# Key_RGB_Sensor_Uart.net
KiCad netlist of a schematic drawn in Altium Designer
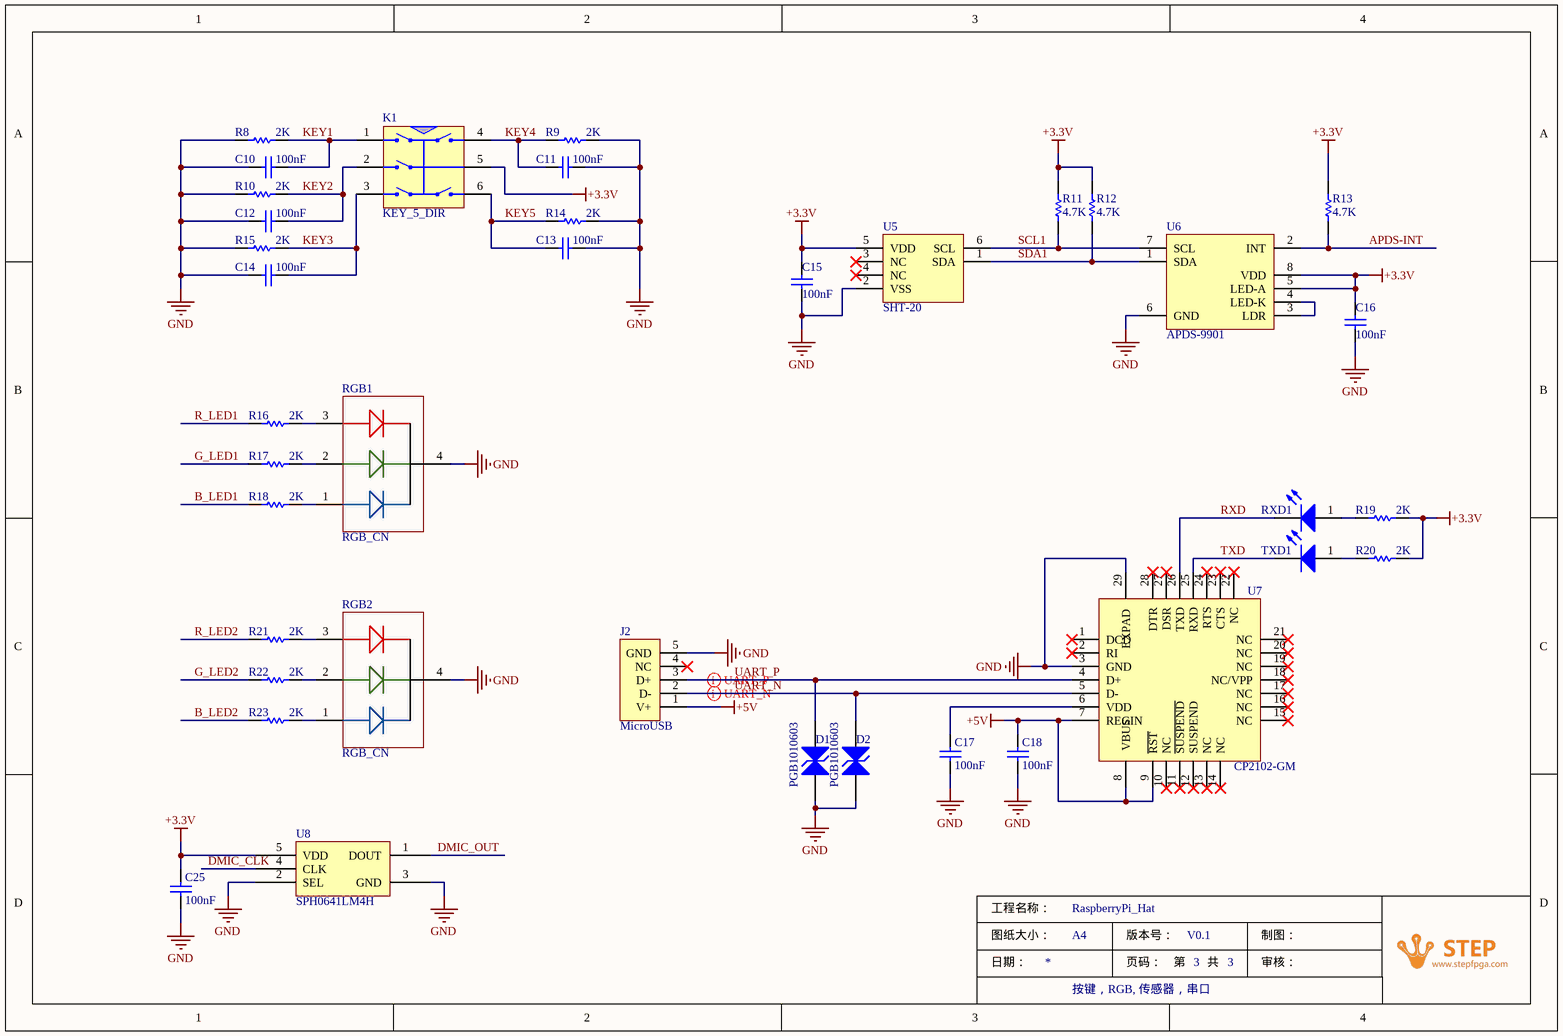
[diagram p0: Key_RGB_Sensor_Uart.SchDoc]

(export (version "E")
  (design (tool "Eeschema 10.0.6"))
  (components
    (comp (ref "C10")
      (value "100nF")
      (footprint "C0603")
      (description "Capacitor (Semiconductor SIM Model)")
      (fields (field (name "PUBLISHER") "Altium Limited"))
      (libsource (lib "Miscellaneous Devices") (part "Cap Semi"))
    )
    (comp (ref "C11")
      (value "100nF")
      (footprint "C0603")
      (description "Capacitor (Semiconductor SIM Model)")
      (fields (field (name "PUBLISHER") "Altium Limited"))
      (libsource (lib "Miscellaneous Devices") (part "Cap Semi"))
    )
    (comp (ref "C12")
      (value "100nF")
      (footprint "C0603")
      (description "Capacitor (Semiconductor SIM Model)")
      (fields (field (name "PUBLISHER") "Altium Limited"))
      (libsource (lib "Miscellaneous Devices") (part "Cap Semi"))
    )
    (comp (ref "C13")
      (value "100nF")
      (footprint "C0603")
      (description "Capacitor (Semiconductor SIM Model)")
      (fields (field (name "PUBLISHER") "Altium Limited"))
      (libsource (lib "Miscellaneous Devices") (part "Cap Semi"))
    )
    (comp (ref "C14")
      (value "100nF")
      (footprint "C0603")
      (description "Capacitor (Semiconductor SIM Model)")
      (fields (field (name "PUBLISHER") "Altium Limited"))
      (libsource (lib "Miscellaneous Devices") (part "Cap Semi"))
    )
    (comp (ref "C15")
      (value "100nF")
      (footprint "C0603")
      (description "Capacitor (Semiconductor SIM Model)")
      (fields (field (name "PUBLISHER") "Altium Limited"))
      (libsource (lib "Miscellaneous Devices") (part "Cap Semi"))
    )
    (comp (ref "C16")
      (value "100nF")
      (footprint "C0603")
      (description "Capacitor (Semiconductor SIM Model)")
      (fields (field (name "PUBLISHER") "Altium Limited"))
      (libsource (lib "Miscellaneous Devices") (part "Cap Semi"))
    )
    (comp (ref "C17")
      (value "100nF")
      (footprint "C0603")
      (description "Capacitor")
      (fields (field (name "PUBLISHER") "Altium Limited"))
      (libsource (lib "Miscellaneous Devices") (part "Cap"))
    )
    (comp (ref "C18")
      (value "100nF")
      (footprint "C0603")
      (description "Capacitor")
      (fields (field (name "PUBLISHER") "Altium Limited"))
      (libsource (lib "Miscellaneous Devices") (part "Cap"))
    )
    (comp (ref "C25")
      (value "100nF")
      (footprint "C0603")
      (description "Capacitor")
      (fields (field (name "PUBLISHER") "Altium Limited"))
      (libsource (lib "Miscellaneous Devices") (part "Cap"))
    )
    (comp (ref "D1")
      (value "PGB1010603")
      (footprint "C0603")
      (description "ESD 抑制器 0603 24VDC .06pF")
      (libsource (lib "FPGA DIP40") (part "PGB1010603"))
    )
    (comp (ref "D2")
      (value "PGB1010603")
      (footprint "C0603")
      (description "ESD 抑制器 0603 24VDC .06pF")
      (libsource (lib "FPGA DIP40") (part "PGB1010603"))
    )
    (comp (ref "J2")
      (value "MicroUSB")
      (footprint "MICRO_USB_4")
      (description "Micro USB Header")
      (libsource (lib "FPGA DIP40") (part "Micro USB Header"))
    )
    (comp (ref "K1")
      (value "KEY_5_DIR")
      (footprint "KEY-CH5")
      (description "五向按键开关，摇杆")
      (libsource (lib "wanganran") (part "KEY_5_DIR"))
    )
    (comp (ref "R8")
      (value "2K")
      (footprint "R0603")
      (description "Resistor")
      (fields (field (name "PUBLISHER") "Altium Limited"))
      (libsource (lib "Miscellaneous Devices") (part "Res1"))
    )
    (comp (ref "R9")
      (value "2K")
      (footprint "R0603")
      (description "Resistor")
      (fields (field (name "PUBLISHER") "Altium Limited"))
      (libsource (lib "Miscellaneous Devices") (part "Res1"))
    )
    (comp (ref "R10")
      (value "2K")
      (footprint "R0603")
      (description "Resistor")
      (fields (field (name "PUBLISHER") "Altium Limited"))
      (libsource (lib "Miscellaneous Devices") (part "Res1"))
    )
    (comp (ref "R11")
      (value "4.7K")
      (footprint "R0603")
      (description "Resistor")
      (fields (field (name "PUBLISHER") "Altium Limited"))
      (libsource (lib "Miscellaneous Devices") (part "Res1"))
    )
    (comp (ref "R12")
      (value "4.7K")
      (footprint "R0603")
      (description "Resistor")
      (fields (field (name "PUBLISHER") "Altium Limited"))
      (libsource (lib "Miscellaneous Devices") (part "Res1"))
    )
    (comp (ref "R13")
      (value "4.7K")
      (footprint "R0603")
      (description "Resistor")
      (fields (field (name "PUBLISHER") "Altium Limited"))
      (libsource (lib "Miscellaneous Devices") (part "Res1"))
    )
    (comp (ref "R14")
      (value "2K")
      (footprint "R0603")
      (description "Resistor")
      (fields (field (name "PUBLISHER") "Altium Limited"))
      (libsource (lib "Miscellaneous Devices") (part "Res1"))
    )
    (comp (ref "R15")
      (value "2K")
      (footprint "R0603")
      (description "Resistor")
      (fields (field (name "PUBLISHER") "Altium Limited"))
      (libsource (lib "Miscellaneous Devices") (part "Res1"))
    )
    (comp (ref "R16")
      (value "2K")
      (footprint "R0603")
      (description "Resistor")
      (fields (field (name "PUBLISHER") "Altium Limited"))
      (libsource (lib "Miscellaneous Devices") (part "Res1"))
    )
    (comp (ref "R17")
      (value "2K")
      (footprint "R0603")
      (description "Resistor")
      (fields (field (name "PUBLISHER") "Altium Limited"))
      (libsource (lib "Miscellaneous Devices") (part "Res1"))
    )
    (comp (ref "R18")
      (value "2K")
      (footprint "R0603")
      (description "Resistor")
      (fields (field (name "PUBLISHER") "Altium Limited"))
      (libsource (lib "Miscellaneous Devices") (part "Res1"))
    )
    (comp (ref "R19")
      (value "2K")
      (footprint "R0603")
      (description "Resistor")
      (fields (field (name "PUBLISHER") "Altium Limited"))
      (libsource (lib "Miscellaneous Devices") (part "Res1"))
    )
    (comp (ref "R20")
      (value "2K")
      (footprint "R0603")
      (description "Resistor")
      (fields (field (name "PUBLISHER") "Altium Limited"))
      (libsource (lib "Miscellaneous Devices") (part "Res1"))
    )
    (comp (ref "R21")
      (value "2K")
      (footprint "R0603")
      (description "Resistor")
      (fields (field (name "PUBLISHER") "Altium Limited"))
      (libsource (lib "Miscellaneous Devices") (part "Res1"))
    )
    (comp (ref "R22")
      (value "2K")
      (footprint "R0603")
      (description "Resistor")
      (fields (field (name "PUBLISHER") "Altium Limited"))
      (libsource (lib "Miscellaneous Devices") (part "Res1"))
    )
    (comp (ref "R23")
      (value "2K")
      (footprint "R0603")
      (description "Resistor")
      (fields (field (name "PUBLISHER") "Altium Limited"))
      (libsource (lib "Miscellaneous Devices") (part "Res1"))
    )
    (comp (ref "RGB1")
      (value "RGB_CN")
      (footprint "RGB_LEDCN")
      (libsource (lib "RaspberryPi_Hat_schlib") (part "RGB_CN"))
    )
    (comp (ref "RGB2")
      (value "RGB_CN")
      (footprint "RGB_LEDCN")
      (libsource (lib "RaspberryPi_Hat_schlib") (part "RGB_CN"))
    )
    (comp (ref "RXD1")
      (value "LED")
      (footprint "LED0603")
      (description "Typical INFRARED GaAs LED,1.8V,10mA,Red")
      (libsource (lib "fpga_board") (part "LED"))
    )
    (comp (ref "TXD1")
      (value "LED")
      (footprint "LED0603")
      (description "Typical INFRARED GaAs LED,1.8V,10mA,Red")
      (libsource (lib "fpga_board") (part "LED"))
    )
    (comp (ref "U5")
      (value "SHT-20")
      (footprint "SHT20")
      (description "温湿度传感器")
      (libsource (lib "step") (part "SHT-20"))
    )
    (comp (ref "U6")
      (value "APDS-9901")
      (footprint "APDS9901")
      (description "接近式传感器")
      (libsource (lib "step") (part "APDS-9901"))
    )
    (comp (ref "U7")
      (value "CP2102-GM")
      (footprint "QFN5*5_28")
      (description "CP2102，USB转串口UART驱动芯片")
      (libsource (lib "wanganran") (part "CP2102"))
    )
    (comp (ref "U8")
      (value "SPH0641LM4H")
      (footprint "SPH(3.5*2.65)")
      (description "数字麦克风")
      (libsource (lib "RaspberryPi_Hat_schlib") (part "SPH0641LM4H"))
    )
  )
  (nets
    (net (code "1") (name "+3.3V") (class "Default")
      (node (ref "C15") (pin "2") (pinfunction "2_2") (pintype "passive"))
      (node (ref "C16") (pin "2") (pinfunction "2_2") (pintype "passive"))
      (node (ref "C25") (pin "2") (pinfunction "2_2") (pintype "passive"))
      (node (ref "K1") (pin "5") (pinfunction "COM_5") (pintype "passive"))
      (node (ref "R11") (pin "2") (pinfunction "2_2") (pintype "passive"))
      (node (ref "R12") (pin "2") (pinfunction "2_2") (pintype "passive"))
      (node (ref "R13") (pin "2") (pinfunction "2_2") (pintype "passive"))
      (node (ref "R19") (pin "1") (pinfunction "1_1") (pintype "passive"))
      (node (ref "R20") (pin "1") (pinfunction "1_1") (pintype "passive"))
      (node (ref "U5") (pin "5") (pinfunction "VDD_5") (pintype "passive"))
      (node (ref "U6") (pin "5") (pinfunction "LED-A_5") (pintype "passive"))
      (node (ref "U6") (pin "8") (pinfunction "VDD_8") (pintype "passive"))
      (node (ref "U8") (pin "5") (pinfunction "VDD_5") (pintype "passive"))
    )
    (net (code "2") (name "+5V") (class "Default")
      (node (ref "C18") (pin "2") (pinfunction "2_2") (pintype "passive"))
      (node (ref "J2") (pin "1") (pinfunction "V+_1") (pintype "passive"))
      (node (ref "U7") (pin "7") (pinfunction "REGIN_7") (pintype "passive"))
      (node (ref "U7") (pin "8") (pinfunction "VBUS_8") (pintype "passive"))
      (node (ref "U7") (pin "9") (pinfunction "~{RST}_9") (pintype "passive"))
    )
    (net (code "3") (name "/APDS-INT") (class "Default")
      (node (ref "R13") (pin "1") (pinfunction "1_1") (pintype "passive"))
      (node (ref "U6") (pin "2") (pinfunction "INT_2") (pintype "passive"))
    )
    (net (code "4") (name "/B_LED1") (class "Default")
      (node (ref "R18") (pin "2") (pinfunction "2_2") (pintype "passive"))
    )
    (net (code "5") (name "/B_LED2") (class "Default")
      (node (ref "R23") (pin "2") (pinfunction "2_2") (pintype "passive"))
    )
    (net (code "6") (name "/DMIC_CLK") (class "Default")
      (node (ref "U8") (pin "4") (pinfunction "CLK_4") (pintype "passive"))
    )
    (net (code "7") (name "/DMIC_OUT") (class "Default")
      (node (ref "U8") (pin "1") (pinfunction "DOUT_1") (pintype "passive"))
    )
    (net (code "8") (name "/G_LED1") (class "Default")
      (node (ref "R17") (pin "2") (pinfunction "2_2") (pintype "passive"))
    )
    (net (code "9") (name "/G_LED2") (class "Default")
      (node (ref "R22") (pin "2") (pinfunction "2_2") (pintype "passive"))
    )
    (net (code "10") (name "/KEY1") (class "Default")
      (node (ref "C10") (pin "1") (pinfunction "1_1") (pintype "passive"))
      (node (ref "K1") (pin "1") (pinfunction "COM_1") (pintype "passive"))
      (node (ref "R8") (pin "1") (pinfunction "1_1") (pintype "passive"))
    )
    (net (code "11") (name "/KEY2") (class "Default")
      (node (ref "C12") (pin "1") (pinfunction "1_1") (pintype "passive"))
      (node (ref "K1") (pin "2") (pinfunction "COM_2") (pintype "passive"))
      (node (ref "R10") (pin "1") (pinfunction "1_1") (pintype "passive"))
    )
    (net (code "12") (name "/KEY3") (class "Default")
      (node (ref "C14") (pin "1") (pinfunction "1_1") (pintype "passive"))
      (node (ref "K1") (pin "3") (pinfunction "COM_3") (pintype "passive"))
      (node (ref "R15") (pin "1") (pinfunction "1_1") (pintype "passive"))
    )
    (net (code "13") (name "/KEY4") (class "Default")
      (node (ref "C11") (pin "2") (pinfunction "2_2") (pintype "passive"))
      (node (ref "K1") (pin "4") (pinfunction "COM_4") (pintype "passive"))
      (node (ref "R9") (pin "2") (pinfunction "2_2") (pintype "passive"))
    )
    (net (code "14") (name "/KEY5") (class "Default")
      (node (ref "C13") (pin "2") (pinfunction "2_2") (pintype "passive"))
      (node (ref "K1") (pin "6") (pinfunction "COM_6") (pintype "passive"))
      (node (ref "R14") (pin "2") (pinfunction "2_2") (pintype "passive"))
    )
    (net (code "15") (name "/RXD") (class "Default")
      (node (ref "RXD1") (pin "2") (pinfunction "K_2") (pintype "passive"))
      (node (ref "U7") (pin "26") (pinfunction "TXD_26") (pintype "passive"))
    )
    (net (code "16") (name "/R_LED1") (class "Default")
      (node (ref "R16") (pin "2") (pinfunction "2_2") (pintype "passive"))
    )
    (net (code "17") (name "/R_LED2") (class "Default")
      (node (ref "R21") (pin "2") (pinfunction "2_2") (pintype "passive"))
    )
    (net (code "18") (name "/SCL1") (class "Default")
      (node (ref "R11") (pin "1") (pinfunction "1_1") (pintype "passive"))
      (node (ref "U5") (pin "6") (pinfunction "SCL_6") (pintype "passive"))
      (node (ref "U6") (pin "7") (pinfunction "SCL_7") (pintype "passive"))
    )
    (net (code "19") (name "/SDA1") (class "Default")
      (node (ref "R12") (pin "1") (pinfunction "1_1") (pintype "passive"))
      (node (ref "U5") (pin "1") (pinfunction "SDA_1") (pintype "passive"))
      (node (ref "U6") (pin "1") (pinfunction "SDA_1") (pintype "passive"))
    )
    (net (code "20") (name "/TXD") (class "Default")
      (node (ref "TXD1") (pin "2") (pinfunction "K_2") (pintype "passive"))
      (node (ref "U7") (pin "25") (pinfunction "RXD_25") (pintype "passive"))
    )
    (net (code "21") (name "/UART_N") (class "Default")
      (node (ref "D2") (pin "2") (pinfunction "K_2") (pintype "passive"))
      (node (ref "J2") (pin "2") (pinfunction "D-_2") (pintype "passive"))
      (node (ref "U7") (pin "5") (pinfunction "D-_5") (pintype "passive"))
    )
    (net (code "22") (name "/UART_P") (class "Default")
      (node (ref "D1") (pin "2") (pinfunction "K_2") (pintype "passive"))
      (node (ref "J2") (pin "3") (pinfunction "D+_3") (pintype "passive"))
      (node (ref "U7") (pin "4") (pinfunction "D+_4") (pintype "passive"))
    )
    (net (code "23") (name "GND") (class "Default")
      (node (ref "C10") (pin "2") (pinfunction "2_2") (pintype "passive"))
      (node (ref "C11") (pin "1") (pinfunction "1_1") (pintype "passive"))
      (node (ref "C12") (pin "2") (pinfunction "2_2") (pintype "passive"))
      (node (ref "C13") (pin "1") (pinfunction "1_1") (pintype "passive"))
      (node (ref "C14") (pin "2") (pinfunction "2_2") (pintype "passive"))
      (node (ref "C15") (pin "1") (pinfunction "1_1") (pintype "passive"))
      (node (ref "C16") (pin "1") (pinfunction "1_1") (pintype "passive"))
      (node (ref "C17") (pin "1") (pinfunction "1_1") (pintype "passive"))
      (node (ref "C18") (pin "1") (pinfunction "1_1") (pintype "passive"))
      (node (ref "C25") (pin "1") (pinfunction "1_1") (pintype "passive"))
      (node (ref "D1") (pin "1") (pinfunction "A_1") (pintype "passive"))
      (node (ref "D2") (pin "1") (pinfunction "A_1") (pintype "passive"))
      (node (ref "J2") (pin "5") (pinfunction "GND_5") (pintype "passive"))
      (node (ref "R10") (pin "2") (pinfunction "2_2") (pintype "passive"))
      (node (ref "R14") (pin "1") (pinfunction "1_1") (pintype "passive"))
      (node (ref "R15") (pin "2") (pinfunction "2_2") (pintype "passive"))
      (node (ref "R8") (pin "2") (pinfunction "2_2") (pintype "passive"))
      (node (ref "R9") (pin "1") (pinfunction "1_1") (pintype "passive"))
      (node (ref "RGB1") (pin "4") (pinfunction "COM_4") (pintype "passive"))
      (node (ref "RGB2") (pin "4") (pinfunction "COM_4") (pintype "passive"))
      (node (ref "U5") (pin "2") (pinfunction "VSS_2") (pintype "passive"))
      (node (ref "U6") (pin "6") (pinfunction "GND_6") (pintype "passive"))
      (node (ref "U7") (pin "29") (pinfunction "EXPAD_29") (pintype "passive"))
      (node (ref "U7") (pin "3") (pinfunction "GND_3") (pintype "passive"))
      (node (ref "U8") (pin "2") (pinfunction "SEL_2") (pintype "passive"))
      (node (ref "U8") (pin "3") (pinfunction "GND_3") (pintype "passive"))
    )
    (net (code "24") (name "Net-(R16-Pad1)") (class "Default")
      (node (ref "R16") (pin "1") (pinfunction "1_1") (pintype "passive"))
      (node (ref "RGB1") (pin "3") (pinfunction "G_3") (pintype "passive"))
    )
    (net (code "25") (name "Net-(R17-Pad1)") (class "Default")
      (node (ref "R17") (pin "1") (pinfunction "1_1") (pintype "passive"))
      (node (ref "RGB1") (pin "2") (pinfunction "G_2") (pintype "passive"))
    )
    (net (code "26") (name "Net-(R21-Pad1)") (class "Default")
      (node (ref "R21") (pin "1") (pinfunction "1_1") (pintype "passive"))
      (node (ref "RGB2") (pin "3") (pinfunction "G_3") (pintype "passive"))
    )
    (net (code "27") (name "Net-(R22-Pad1)") (class "Default")
      (node (ref "R22") (pin "1") (pinfunction "1_1") (pintype "passive"))
      (node (ref "RGB2") (pin "2") (pinfunction "G_2") (pintype "passive"))
    )
    (net (code "28") (name "Net-(RGB1-B)") (class "Default")
      (node (ref "R18") (pin "1") (pinfunction "1_1") (pintype "passive"))
      (node (ref "RGB1") (pin "1") (pinfunction "B_1") (pintype "passive"))
    )
    (net (code "29") (name "Net-(RGB2-B)") (class "Default")
      (node (ref "R23") (pin "1") (pinfunction "1_1") (pintype "passive"))
      (node (ref "RGB2") (pin "1") (pinfunction "B_1") (pintype "passive"))
    )
    (net (code "30") (name "Net-(RXD1-A)") (class "Default")
      (node (ref "R19") (pin "2") (pinfunction "2_2") (pintype "passive"))
      (node (ref "RXD1") (pin "1") (pinfunction "A_1") (pintype "passive"))
    )
    (net (code "31") (name "Net-(TXD1-A)") (class "Default")
      (node (ref "R20") (pin "2") (pinfunction "2_2") (pintype "passive"))
      (node (ref "TXD1") (pin "1") (pinfunction "A_1") (pintype "passive"))
    )
    (net (code "32") (name "Net-(U6-LDR)") (class "Default")
      (node (ref "U6") (pin "3") (pinfunction "LDR_3") (pintype "passive"))
      (node (ref "U6") (pin "4") (pinfunction "LED-K_4") (pintype "passive"))
    )
    (net (code "33") (name "Net-(U7-VDD)") (class "Default")
      (node (ref "C17") (pin "2") (pinfunction "2_2") (pintype "passive"))
      (node (ref "U7") (pin "6") (pinfunction "VDD_6") (pintype "passive"))
    )
    (net (code "34") (name "unconnected-(J2-NC-Pad4)") (class "Default")
      (node (ref "J2") (pin "4") (pinfunction "NC_4") (pintype "passive+no_connect"))
    )
    (net (code "35") (name "unconnected-(U5-NC-Pad3)") (class "Default")
      (node (ref "U5") (pin "3") (pinfunction "NC_3") (pintype "passive+no_connect"))
    )
    (net (code "36") (name "unconnected-(U5-NC-Pad4)") (class "Default")
      (node (ref "U5") (pin "4") (pinfunction "NC_4") (pintype "passive+no_connect"))
    )
    (net (code "37") (name "unconnected-(U7-CTS-Pad23)") (class "Default")
      (node (ref "U7") (pin "23") (pinfunction "CTS_23") (pintype "passive+no_connect"))
    )
    (net (code "38") (name "unconnected-(U7-DCD-Pad1)") (class "Default")
      (node (ref "U7") (pin "1") (pinfunction "DCD_1") (pintype "passive+no_connect"))
    )
    (net (code "39") (name "unconnected-(U7-DSR-Pad27)") (class "Default")
      (node (ref "U7") (pin "27") (pinfunction "DSR_27") (pintype "passive+no_connect"))
    )
    (net (code "40") (name "unconnected-(U7-DTR-Pad28)") (class "Default")
      (node (ref "U7") (pin "28") (pinfunction "DTR_28") (pintype "passive+no_connect"))
    )
    (net (code "41") (name "unconnected-(U7-NC-Pad10)") (class "Default")
      (node (ref "U7") (pin "10") (pinfunction "NC_10") (pintype "passive+no_connect"))
    )
    (net (code "42") (name "unconnected-(U7-NC-Pad13)") (class "Default")
      (node (ref "U7") (pin "13") (pinfunction "NC_13") (pintype "passive+no_connect"))
    )
    (net (code "43") (name "unconnected-(U7-NC-Pad14)") (class "Default")
      (node (ref "U7") (pin "14") (pinfunction "NC_14") (pintype "passive+no_connect"))
    )
    (net (code "44") (name "unconnected-(U7-NC-Pad15)") (class "Default")
      (node (ref "U7") (pin "15") (pinfunction "NC_15") (pintype "passive+no_connect"))
    )
    (net (code "45") (name "unconnected-(U7-NC-Pad16)") (class "Default")
      (node (ref "U7") (pin "16") (pinfunction "NC_16") (pintype "passive+no_connect"))
    )
    (net (code "46") (name "unconnected-(U7-NC-Pad17)") (class "Default")
      (node (ref "U7") (pin "17") (pinfunction "NC_17") (pintype "passive+no_connect"))
    )
    (net (code "47") (name "unconnected-(U7-NC-Pad19)") (class "Default")
      (node (ref "U7") (pin "19") (pinfunction "NC_19") (pintype "passive+no_connect"))
    )
    (net (code "48") (name "unconnected-(U7-NC-Pad20)") (class "Default")
      (node (ref "U7") (pin "20") (pinfunction "NC_20") (pintype "passive+no_connect"))
    )
    (net (code "49") (name "unconnected-(U7-NC-Pad21)") (class "Default")
      (node (ref "U7") (pin "21") (pinfunction "NC_21") (pintype "passive+no_connect"))
    )
    (net (code "50") (name "unconnected-(U7-NC-Pad22)") (class "Default")
      (node (ref "U7") (pin "22") (pinfunction "NC_22") (pintype "passive+no_connect"))
    )
    (net (code "51") (name "unconnected-(U7-NC{slash}VPP-Pad18)") (class "Default")
      (node (ref "U7") (pin "18") (pinfunction "NC/VPP_18") (pintype "passive+no_connect"))
    )
    (net (code "52") (name "unconnected-(U7-RI-Pad2)") (class "Default")
      (node (ref "U7") (pin "2") (pinfunction "RI_2") (pintype "passive+no_connect"))
    )
    (net (code "53") (name "unconnected-(U7-RTS-Pad24)") (class "Default")
      (node (ref "U7") (pin "24") (pinfunction "RTS_24") (pintype "passive+no_connect"))
    )
    (net (code "54") (name "unconnected-(U7-SUSPEND-Pad12)") (class "Default")
      (node (ref "U7") (pin "12") (pinfunction "SUSPEND_12") (pintype "passive+no_connect"))
    )
    (net (code "55") (name "unconnected-(U7-~{SUSPEND}-Pad11)") (class "Default")
      (node (ref "U7") (pin "11") (pinfunction "~{SUSPEND}_11") (pintype "passive+no_connect"))
    )
  )
)
